# design.net
KiCad netlist of a schematic drawn in Altium Designer
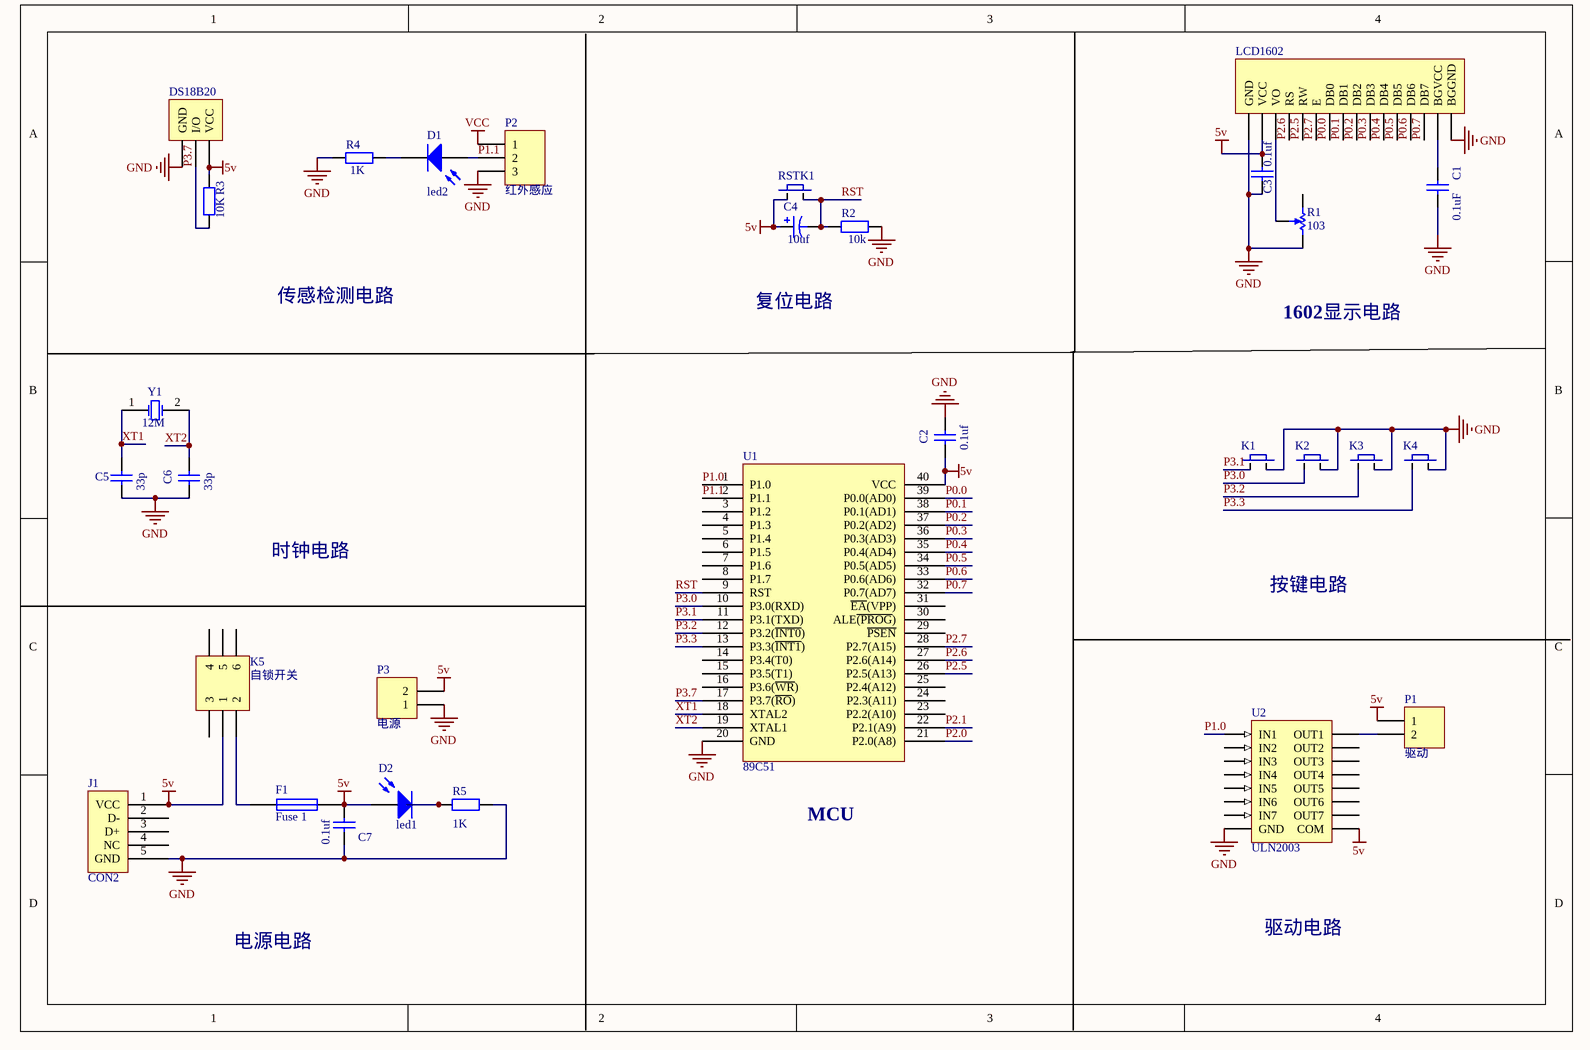
[diagram p0: 智能温控风扇.SchDoc]

(export (version "E")
  (design (tool "Eeschema 10.0.6"))
  (components
    (comp (ref "C1")
      (value "0.1uF")
      (footprint "CAP-CT4G-0805-5.08MM")
      (description "Capacitor")
      (fields (field (name "Comment") "Cap") (field (name "PUBLISHER") "Altium Limited"))
      (libsource (lib "Miscellaneous Devices") (part "Cap"))
    )
    (comp (ref "C2")
      (value "0.1uf")
      (footprint "CAP-CT4G-0805-5.08MM")
      (description "Capacitor")
      (fields (field (name "Comment") "Cap") (field (name "PUBLISHER") "Altium Limited"))
      (libsource (lib "Miscellaneous Devices") (part "Cap"))
    )
    (comp (ref "C3")
      (value "0.1uf")
      (footprint "CAP-CT4G-0805-5.08MM")
      (description "Capacitor")
      (fields (field (name "Comment") "Cap") (field (name "PUBLISHER") "Altium Limited"))
      (libsource (lib "Miscellaneous Devices") (part "Cap"))
    )
    (comp (ref "C4")
      (value "10uf")
      (footprint "CAP-D4.0XF1.5")
      (description "Polarized Capacitor (Radial)")
      (fields (field (name "Comment") "Cap Pol1") (field (name "PUBLISHER") "Altium Limited"))
      (libsource (lib "Miscellaneous Devices") (part "Cap Pol1"))
    )
    (comp (ref "C5")
      (value "33p")
      (footprint "CAP-CT4G-0805-5.08MM")
      (description "Capacitor")
      (fields (field (name "Comment") "Cap") (field (name "PUBLISHER") "Altium Limited"))
      (libsource (lib "Miscellaneous Devices") (part "Cap"))
    )
    (comp (ref "C6")
      (value "33p")
      (footprint "CAP-CT4G-0805-5.08MM")
      (description "Capacitor")
      (fields (field (name "Comment") "Cap") (field (name "PUBLISHER") "Altium Limited"))
      (libsource (lib "Miscellaneous Devices") (part "Cap"))
    )
    (comp (ref "C7")
      (value "0.1uf")
      (footprint "CAP-CT4G-0805-5.08MM")
      (description "Capacitor")
      (fields (field (name "Comment") "Cap") (field (name "PUBLISHER") "Altium Limited"))
      (libsource (lib "Miscellaneous Devices") (part "Cap"))
    )
    (comp (ref "D1")
      (value "led2")
      (footprint "LED-5MM-2.54MM")
      (description "Photosensitive Diode")
      (fields (field (name "PUBLISHER") "Altium Limited"))
      (libsource (lib "Miscellaneous Devices") (part "Photo Sen"))
    )
    (comp (ref "D2")
      (value "led1")
      (footprint "LED-5MM-2.54MM")
      (description "Photosensitive Diode")
      (fields (field (name "PUBLISHER") "Altium Limited"))
      (libsource (lib "Miscellaneous Devices") (part "Photo Sen"))
    )
    (comp (ref "DS18B20")
      (value "温度传感器")
      (footprint "HDR1X3")
      (description "Header, 3-Pin")
      (fields (field (name "PUBLISHER") "Altium Limited"))
      (libsource (lib "核心板") (part "Header 3"))
    )
    (comp (ref "F1")
      (value "Fuse 1")
      (footprint "PIN-W2/E2.8")
      (description "Fuse")
      (fields (field (name "PUBLISHER") "Altium Limited"))
      (libsource (lib "Miscellaneous Devices") (part "Fuse 1"))
    )
    (comp (ref "J1") (value "CON2") (footprint "MicroUSB1") (libsource (lib "89C51") (part "CON2_1")))
    (comp (ref "K1") (value "轻触按键") (footprint "独立按键") (libsource (lib "核心板") (part "轻触按键")))
    (comp (ref "K2") (value "轻触按键") (footprint "独立按键") (libsource (lib "核心板") (part "轻触按键")))
    (comp (ref "K3") (value "轻触按键") (footprint "独立按键") (libsource (lib "核心板") (part "轻触按键")))
    (comp (ref "K4") (value "轻触按键") (footprint "独立按键") (libsource (lib "核心板") (part "轻触按键")))
    (comp (ref "K5")
      (value "自锁开关")
      (footprint "SWICH - duplicate")
      (description "Header, 3-Pin, Dual row")
      (fields (field (name "PUBLISHER") "Altium Limited"))
      (libsource (lib "核心板") (part "Header 3X2A"))
    )
    (comp (ref "LCD1602")
      (value "舵机")
      (footprint "MHDR1X16")
      (description "Header, 3-Pin")
      (fields (field (name "PUBLISHER") "Altium Limited"))
      (libsource (lib "核心板") (part "MHDR1X3"))
    )
    (comp (ref "P1")
      (value "驱动")
      (footprint "HDR1X2")
      (description "Header, 2-Pin")
      (fields (field (name "PUBLISHER") "Altium Limited"))
      (libsource (lib "") (part "Header 2_1"))
    )
    (comp (ref "P2")
      (value "红外感应")
      (footprint "HDR1X3")
      (description "Header, 3-Pin")
      (fields (field (name "PUBLISHER") "Altium Limited"))
      (libsource (lib "Miscellaneous Connectors") (part "Header 3"))
    )
    (comp (ref "P3")
      (value "电源")
      (footprint "HDR1X2")
      (description "Header, 2-Pin")
      (fields (field (name "PUBLISHER") "Altium Limited"))
      (libsource (lib "核心板") (part "Header 2"))
    )
    (comp (ref "R1")
      (value "103")
      (footprint "RES-ADJ_3362P")
      (description "Square Trimming Potentiometer")
      (fields (field (name "PUBLISHER") "Altium Limited"))
      (libsource (lib "Miscellaneous Devices") (part "RPot SM"))
    )
    (comp (ref "R2")
      (value "10k")
      (footprint "AXIAL-11.5X4.5(2WS)")
      (description "Resistor")
      (fields (field (name "Comment") "Res2") (field (name "PUBLISHER") "Altium Limited"))
      (libsource (lib "") (part "Res2_2"))
    )
    (comp (ref "R3")
      (value "10K")
      (footprint "AXIAL-0.4")
      (description "Resistor")
      (fields (field (name "Comment") "Res2") (field (name "PUBLISHER") "Altium Limited"))
      (libsource (lib "") (part "Res2_1"))
    )
    (comp (ref "R4")
      (value "1K")
      (footprint "AXIAL-0.4")
      (description "Resistor")
      (fields (field (name "Comment") "Res2") (field (name "PUBLISHER") "Altium Limited"))
      (libsource (lib "Miscellaneous Devices") (part "Res2"))
    )
    (comp (ref "R5")
      (value "1K")
      (footprint "AXIAL-0.6")
      (description "Resistor")
      (fields (field (name "Comment") "Res2") (field (name "PUBLISHER") "Altium Limited"))
      (libsource (lib "") (part "Res2_2"))
    )
    (comp (ref "RSTK1") (value "轻触按键") (footprint "独立按键") (libsource (lib "核心板") (part "轻触按键")))
    (comp (ref "U1") (value "89C51") (footprint "89c51") (libsource (lib "89C51") (part "89C51")))
    (comp (ref "U2")
      (value "ULN2003")
      (footprint "PDIP-16")
      (description "Header, 9-Pin, Dual row")
      (fields (field (name "PUBLISHER") "Altium Limited"))
      (libsource (lib "核心板") (part "Header 9X2"))
    )
    (comp (ref "Y1")
      (value "12M")
      (footprint "XTAL")
      (description "Crystal Oscillator")
      (fields (field (name "PUBLISHER") "Altium Limited"))
      (libsource (lib "Miscellaneous Devices") (part "XTAL"))
    )
  )
  (nets
    (net (code "1") (name "/P0.0") (class "Default")
      (node (ref "LCD1602") (pin "3") (pinfunction "DB0_3") (pintype "passive"))
      (node (ref "U1") (pin "39") (pinfunction "P0.0(AD0)_39") (pintype "passive"))
    )
    (net (code "2") (name "/P0.1") (class "Default")
      (node (ref "LCD1602") (pin "3") (pinfunction "DB1_3") (pintype "passive"))
      (node (ref "U1") (pin "38") (pinfunction "P0.1(AD1)_38") (pintype "passive"))
    )
    (net (code "3") (name "/P0.2") (class "Default")
      (node (ref "LCD1602") (pin "3") (pinfunction "DB2_3") (pintype "passive"))
      (node (ref "U1") (pin "37") (pinfunction "P0.2(AD2)_37") (pintype "passive"))
    )
    (net (code "4") (name "/P0.3") (class "Default")
      (node (ref "LCD1602") (pin "3") (pinfunction "DB3_3") (pintype "passive"))
      (node (ref "U1") (pin "36") (pinfunction "P0.3(AD3)_36") (pintype "passive"))
    )
    (net (code "5") (name "/P0.4") (class "Default")
      (node (ref "LCD1602") (pin "3") (pinfunction "DB4_3") (pintype "passive"))
      (node (ref "U1") (pin "35") (pinfunction "P0.4(AD4)_35") (pintype "passive"))
    )
    (net (code "6") (name "/P0.5") (class "Default")
      (node (ref "LCD1602") (pin "3") (pinfunction "DB5_3") (pintype "passive"))
      (node (ref "U1") (pin "34") (pinfunction "P0.5(AD5)_34") (pintype "passive"))
    )
    (net (code "7") (name "/P0.6") (class "Default")
      (node (ref "LCD1602") (pin "3") (pinfunction "DB6_3") (pintype "passive"))
      (node (ref "U1") (pin "33") (pinfunction "P0.6(AD6)_33") (pintype "passive"))
    )
    (net (code "8") (name "/P0.7") (class "Default")
      (node (ref "LCD1602") (pin "3") (pinfunction "DB7_3") (pintype "passive"))
      (node (ref "U1") (pin "32") (pinfunction "P0.7(AD7)_32") (pintype "passive"))
    )
    (net (code "9") (name "/P1.0") (class "Default")
      (node (ref "U1") (pin "1") (pinfunction "P1.0_1") (pintype "passive"))
      (node (ref "U2") (pin "1") (pinfunction "IN1_1") (pintype "input"))
    )
    (net (code "10") (name "/P1.1") (class "Default")
      (node (ref "D1") (pin "1") (pinfunction "A_1") (pintype "passive"))
      (node (ref "P2") (pin "2") (pinfunction "2_2") (pintype "passive"))
      (node (ref "U1") (pin "2") (pinfunction "P1.1_2") (pintype "passive"))
    )
    (net (code "11") (name "/P2.0") (class "Default")
      (node (ref "U1") (pin "21") (pinfunction "P2.0(A8)_21") (pintype "passive"))
    )
    (net (code "12") (name "/P2.1") (class "Default")
      (node (ref "U1") (pin "22") (pinfunction "P2.1(A9)_22") (pintype "passive"))
    )
    (net (code "13") (name "/P2.5") (class "Default")
      (node (ref "LCD1602") (pin "3") (pinfunction "RW_3") (pintype "passive"))
      (node (ref "U1") (pin "26") (pinfunction "P2.5(A13)_26") (pintype "passive"))
    )
    (net (code "14") (name "/P2.6") (class "Default")
      (node (ref "LCD1602") (pin "3") (pinfunction "RS_3") (pintype "passive"))
      (node (ref "U1") (pin "27") (pinfunction "P2.6(A14)_27") (pintype "passive"))
    )
    (net (code "15") (name "/P2.7") (class "Default")
      (node (ref "LCD1602") (pin "3") (pinfunction "E_3") (pintype "passive"))
      (node (ref "U1") (pin "28") (pinfunction "P2.7(A15)_28") (pintype "passive"))
    )
    (net (code "16") (name "/P3.0") (class "Default")
      (node (ref "K2") (pin "0") (pinfunction "0_0") (pintype "passive"))
      (node (ref "U1") (pin "10") (pinfunction "P3.0(RXD)_10") (pintype "passive"))
    )
    (net (code "17") (name "/P3.1") (class "Default")
      (node (ref "K1") (pin "0") (pinfunction "0_0") (pintype "passive"))
      (node (ref "U1") (pin "11") (pinfunction "P3.1(TXD)_11") (pintype "passive"))
    )
    (net (code "18") (name "/P3.2") (class "Default")
      (node (ref "K3") (pin "0") (pinfunction "0_0") (pintype "passive"))
      (node (ref "U1") (pin "12") (pinfunction "P3.2(~{INT0})_12") (pintype "passive"))
    )
    (net (code "19") (name "/P3.3") (class "Default")
      (node (ref "K4") (pin "0") (pinfunction "0_0") (pintype "passive"))
      (node (ref "U1") (pin "13") (pinfunction "P3.3(~{INT1})_13") (pintype "passive"))
    )
    (net (code "20") (name "/P3.7") (class "Default")
      (node (ref "DS18B20") (pin "2") (pinfunction "I/O_2") (pintype "passive"))
      (node (ref "R3") (pin "1") (pinfunction "1_1") (pintype "passive"))
      (node (ref "U1") (pin "17") (pinfunction "P3.7(~{RO})_17") (pintype "passive"))
    )
    (net (code "21") (name "/RST") (class "Default")
      (node (ref "C4") (pin "2") (pinfunction "2_2") (pintype "passive"))
      (node (ref "R2") (pin "1") (pinfunction "1_1") (pintype "passive"))
      (node (ref "RSTK1") (pin "0") (pinfunction "0_0") (pintype "passive"))
      (node (ref "U1") (pin "9") (pinfunction "RST_9") (pintype "passive"))
    )
    (net (code "22") (name "/XT1") (class "Default")
      (node (ref "C5") (pin "2") (pinfunction "2_2") (pintype "passive"))
      (node (ref "U1") (pin "18") (pinfunction "XTAL2_18") (pintype "passive"))
      (node (ref "Y1") (pin "1") (pinfunction "OSC1_1") (pintype "passive"))
    )
    (net (code "23") (name "/XT2") (class "Default")
      (node (ref "C6") (pin "2") (pinfunction "2_2") (pintype "passive"))
      (node (ref "U1") (pin "19") (pinfunction "XTAL1_19") (pintype "passive"))
      (node (ref "Y1") (pin "2") (pinfunction "OSC2_2") (pintype "passive"))
    )
    (net (code "24") (name "5v") (class "Default")
      (node (ref "C2") (pin "1") (pinfunction "1_1") (pintype "passive"))
      (node (ref "C3") (pin "2") (pinfunction "2_2") (pintype "passive"))
      (node (ref "C4") (pin "1") (pinfunction "1_1") (pintype "passive"))
      (node (ref "C7") (pin "1") (pinfunction "1_1") (pintype "passive"))
      (node (ref "D2") (pin "1") (pinfunction "A_1") (pintype "passive"))
      (node (ref "DS18B20") (pin "3") (pinfunction "VCC_3") (pintype "passive"))
      (node (ref "F1") (pin "2") (pinfunction "2_2") (pintype "passive"))
      (node (ref "J1") (pin "1") (pinfunction "VCC_1") (pintype "passive"))
      (node (ref "K5") (pin "1") (pinfunction "1_1") (pintype "passive"))
      (node (ref "LCD1602") (pin "2") (pinfunction "VCC_2") (pintype "passive"))
      (node (ref "P1") (pin "1") (pinfunction "1_1") (pintype "passive"))
      (node (ref "P3") (pin "2") (pinfunction "2_2") (pintype "passive"))
      (node (ref "R3") (pin "2") (pinfunction "2_2") (pintype "passive"))
      (node (ref "RSTK1") (pin "0") (pinfunction "0_0") (pintype "passive"))
      (node (ref "U1") (pin "40") (pinfunction "VCC_40") (pintype "passive"))
      (node (ref "U2") (pin "2") (pinfunction "COM_2") (pintype "passive"))
    )
    (net (code "25") (name "GND") (class "Default")
      (node (ref "C1") (pin "1") (pinfunction "1_1") (pintype "passive"))
      (node (ref "C2") (pin "2") (pinfunction "2_2") (pintype "passive"))
      (node (ref "C3") (pin "1") (pinfunction "1_1") (pintype "passive"))
      (node (ref "C5") (pin "1") (pinfunction "1_1") (pintype "passive"))
      (node (ref "C6") (pin "1") (pinfunction "1_1") (pintype "passive"))
      (node (ref "C7") (pin "2") (pinfunction "2_2") (pintype "passive"))
      (node (ref "DS18B20") (pin "1") (pinfunction "GND_1") (pintype "passive"))
      (node (ref "J1") (pin "5") (pinfunction "GND_5") (pintype "passive"))
      (node (ref "K1") (pin "0") (pinfunction "0_0") (pintype "passive"))
      (node (ref "K2") (pin "0") (pinfunction "0_0") (pintype "passive"))
      (node (ref "K3") (pin "0") (pinfunction "0_0") (pintype "passive"))
      (node (ref "K4") (pin "0") (pinfunction "0_0") (pintype "passive"))
      (node (ref "LCD1602") (pin "1") (pinfunction "GND_1") (pintype "passive"))
      (node (ref "LCD1602") (pin "3") (pinfunction "BGGND_3") (pintype "passive"))
      (node (ref "P2") (pin "3") (pinfunction "3_3") (pintype "passive"))
      (node (ref "P3") (pin "1") (pinfunction "1_1") (pintype "passive"))
      (node (ref "R1") (pin "CW") (pinfunction "+_CW") (pintype "passive"))
      (node (ref "R2") (pin "2") (pinfunction "2_2") (pintype "passive"))
      (node (ref "R4") (pin "2") (pinfunction "2_2") (pintype "passive"))
      (node (ref "R5") (pin "2") (pinfunction "2_2") (pintype "passive"))
      (node (ref "U1") (pin "20") (pinfunction "GND_20") (pintype "passive"))
      (node (ref "U2") (pin "5") (pinfunction "GND_5") (pintype "passive"))
    )
    (net (code "26") (name "Net-(D1-K)") (class "Default")
      (node (ref "D1") (pin "2") (pinfunction "K_2") (pintype "passive"))
      (node (ref "R4") (pin "1") (pinfunction "1_1") (pintype "passive"))
    )
    (net (code "27") (name "Net-(D2-K)") (class "Default")
      (node (ref "D2") (pin "2") (pinfunction "K_2") (pintype "passive"))
      (node (ref "R5") (pin "1") (pinfunction "1_1") (pintype "passive"))
    )
    (net (code "28") (name "Net-(F1-Pad1)") (class "Default")
      (node (ref "F1") (pin "1") (pinfunction "1_1") (pintype "passive"))
      (node (ref "K5") (pin "2") (pinfunction "2_2") (pintype "passive"))
    )
    (net (code "29") (name "Net-(LCD1602-BGVCC)") (class "Default")
      (node (ref "C1") (pin "2") (pinfunction "2_2") (pintype "passive"))
      (node (ref "LCD1602") (pin "3") (pinfunction "BGVCC_3") (pintype "passive"))
    )
    (net (code "30") (name "Net-(LCD1602-VO)") (class "Default")
      (node (ref "LCD1602") (pin "3") (pinfunction "VO_3") (pintype "passive"))
      (node (ref "R1") (pin "W") (pinfunction "W_W") (pintype "passive"))
    )
    (net (code "31") (name "Net-(U2-OUT1)") (class "Default")
      (node (ref "P1") (pin "2") (pinfunction "2_2") (pintype "passive"))
      (node (ref "U2") (pin "2") (pinfunction "OUT1_2") (pintype "passive"))
    )
    (net (code "32") (name "VCC") (class "Default")
      (node (ref "P2") (pin "1") (pinfunction "1_1") (pintype "passive"))
    )
    (net (code "33") (name "unconnected-(J1-D+-Pad3)") (class "Default")
      (node (ref "J1") (pin "3") (pinfunction "D+_3") (pintype "passive"))
    )
    (net (code "34") (name "unconnected-(J1-D--Pad2)") (class "Default")
      (node (ref "J1") (pin "2") (pinfunction "D-_2") (pintype "passive"))
    )
    (net (code "35") (name "unconnected-(J1-NC-Pad4)") (class "Default")
      (node (ref "J1") (pin "4") (pinfunction "NC_4") (pintype "passive"))
    )
    (net (code "36") (name "unconnected-(K5-Pad3)") (class "Default")
      (node (ref "K5") (pin "3") (pinfunction "3_3") (pintype "passive"))
    )
    (net (code "37") (name "unconnected-(K5-Pad4)") (class "Default")
      (node (ref "K5") (pin "4") (pinfunction "4_4") (pintype "passive"))
    )
    (net (code "38") (name "unconnected-(K5-Pad5)") (class "Default")
      (node (ref "K5") (pin "5") (pinfunction "5_5") (pintype "passive"))
    )
    (net (code "39") (name "unconnected-(K5-Pad6)") (class "Default")
      (node (ref "K5") (pin "6") (pinfunction "6_6") (pintype "passive"))
    )
    (net (code "40") (name "unconnected-(R1---PadCCW)") (class "Default")
      (node (ref "R1") (pin "CCW") (pinfunction "-_CCW") (pintype "passive"))
    )
    (net (code "41") (name "unconnected-(U1-ALE~{(PROG})-Pad30)") (class "Default")
      (node (ref "U1") (pin "30") (pinfunction "ALE~{(PROG})_30") (pintype "passive"))
    )
    (net (code "42") (name "unconnected-(U1-P1.2-Pad3)") (class "Default")
      (node (ref "U1") (pin "3") (pinfunction "P1.2_3") (pintype "passive"))
    )
    (net (code "43") (name "unconnected-(U1-P1.3-Pad4)") (class "Default")
      (node (ref "U1") (pin "4") (pinfunction "P1.3_4") (pintype "passive"))
    )
    (net (code "44") (name "unconnected-(U1-P1.4-Pad5)") (class "Default")
      (node (ref "U1") (pin "5") (pinfunction "P1.4_5") (pintype "passive"))
    )
    (net (code "45") (name "unconnected-(U1-P1.5-Pad6)") (class "Default")
      (node (ref "U1") (pin "6") (pinfunction "P1.5_6") (pintype "passive"))
    )
    (net (code "46") (name "unconnected-(U1-P1.6-Pad7)") (class "Default")
      (node (ref "U1") (pin "7") (pinfunction "P1.6_7") (pintype "passive"))
    )
    (net (code "47") (name "unconnected-(U1-P1.7-Pad8)") (class "Default")
      (node (ref "U1") (pin "8") (pinfunction "P1.7_8") (pintype "passive"))
    )
    (net (code "48") (name "unconnected-(U1-P2.2(A10)-Pad23)") (class "Default")
      (node (ref "U1") (pin "23") (pinfunction "P2.2(A10)_23") (pintype "passive"))
    )
    (net (code "49") (name "unconnected-(U1-P2.3(A11)-Pad24)") (class "Default")
      (node (ref "U1") (pin "24") (pinfunction "P2.3(A11)_24") (pintype "passive"))
    )
    (net (code "50") (name "unconnected-(U1-P2.4(A12)-Pad25)") (class "Default")
      (node (ref "U1") (pin "25") (pinfunction "P2.4(A12)_25") (pintype "passive"))
    )
    (net (code "51") (name "unconnected-(U1-P3.4(T0)-Pad14)") (class "Default")
      (node (ref "U1") (pin "14") (pinfunction "P3.4(T0)_14") (pintype "passive"))
    )
    (net (code "52") (name "unconnected-(U1-P3.5(T1)-Pad15)") (class "Default")
      (node (ref "U1") (pin "15") (pinfunction "P3.5(T1)_15") (pintype "passive"))
    )
    (net (code "53") (name "unconnected-(U1-P3.6(~{WR})-Pad16)") (class "Default")
      (node (ref "U1") (pin "16") (pinfunction "P3.6(~{WR})_16") (pintype "passive"))
    )
    (net (code "54") (name "unconnected-(U1-~{EA}(VPP)-Pad31)") (class "Default")
      (node (ref "U1") (pin "31") (pinfunction "~{EA}(VPP)_31") (pintype "passive"))
    )
    (net (code "55") (name "unconnected-(U1-~{PSEN}-Pad29)") (class "Default")
      (node (ref "U1") (pin "29") (pinfunction "~{PSEN}_29") (pintype "passive"))
    )
    (net (code "56") (name "unconnected-(U2-IN2-Pad2)") (class "Default")
      (node (ref "U2") (pin "2") (pinfunction "IN2_2") (pintype "input"))
    )
    (net (code "57") (name "unconnected-(U2-IN3-Pad5)") (class "Default")
      (node (ref "U2") (pin "5") (pinfunction "IN3_5") (pintype "input"))
    )
    (net (code "58") (name "unconnected-(U2-IN4-Pad5)") (class "Default")
      (node (ref "U2") (pin "5") (pinfunction "IN4_5") (pintype "input"))
    )
    (net (code "59") (name "unconnected-(U2-IN5-Pad5)") (class "Default")
      (node (ref "U2") (pin "5") (pinfunction "IN5_5") (pintype "input"))
    )
    (net (code "60") (name "unconnected-(U2-IN6-Pad5)") (class "Default")
      (node (ref "U2") (pin "5") (pinfunction "IN6_5") (pintype "input"))
    )
    (net (code "61") (name "unconnected-(U2-IN7-Pad5)") (class "Default")
      (node (ref "U2") (pin "5") (pinfunction "IN7_5") (pintype "input"))
    )
    (net (code "62") (name "unconnected-(U2-OUT2-Pad2)") (class "Default")
      (node (ref "U2") (pin "2") (pinfunction "OUT2_2") (pintype "passive"))
    )
    (net (code "63") (name "unconnected-(U2-OUT3-Pad2)") (class "Default")
      (node (ref "U2") (pin "2") (pinfunction "OUT3_2") (pintype "passive"))
    )
    (net (code "64") (name "unconnected-(U2-OUT4-Pad2)") (class "Default")
      (node (ref "U2") (pin "2") (pinfunction "OUT4_2") (pintype "passive"))
    )
    (net (code "65") (name "unconnected-(U2-OUT5-Pad2)") (class "Default")
      (node (ref "U2") (pin "2") (pinfunction "OUT5_2") (pintype "passive"))
    )
    (net (code "66") (name "unconnected-(U2-OUT6-Pad2)") (class "Default")
      (node (ref "U2") (pin "2") (pinfunction "OUT6_2") (pintype "passive"))
    )
    (net (code "67") (name "unconnected-(U2-OUT7-Pad2)") (class "Default")
      (node (ref "U2") (pin "2") (pinfunction "OUT7_2") (pintype "passive"))
    )
  )
)
